# Sheet0-MCU.net
KiCad netlist of a schematic drawn in Altium Designer
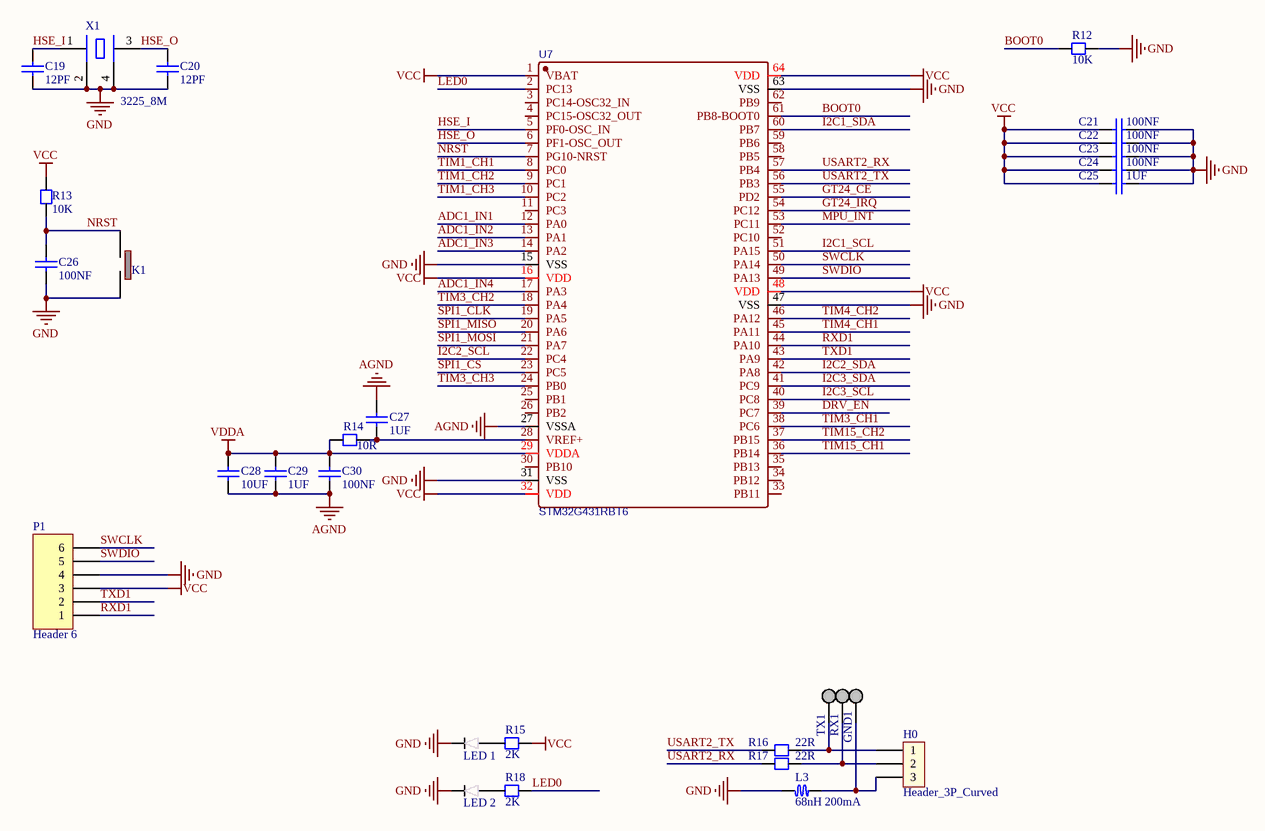
[diagram p0: Sheet0-MCU.SchDoc]

(export (version "E")
  (design (tool "Eeschema 10.0.6"))
  (components
    (comp (ref "C19")
      (value "12PF")
      (footprint "CC1608-0603")
      (description "0603封装的电容")
      (fields (field (name "PUBLISHER") "Altium Limited"))
      (libsource (lib "base") (part "Cap Chip 0603"))
    )
    (comp (ref "C20")
      (value "12PF")
      (footprint "CC1608-0603")
      (description "0603封装的电容")
      (fields (field (name "PUBLISHER") "Altium Limited"))
      (libsource (lib "base") (part "Cap Chip 0603"))
    )
    (comp (ref "C21")
      (value "100NF")
      (footprint "CC1608-0603")
      (description "0603封装的电容")
      (fields (field (name "PUBLISHER") "Altium Limited"))
      (libsource (lib "base") (part "Cap Chip 0603"))
    )
    (comp (ref "C22")
      (value "100NF")
      (footprint "CC1608-0603")
      (description "0603封装的电容")
      (fields (field (name "PUBLISHER") "Altium Limited"))
      (libsource (lib "base") (part "Cap Chip 0603"))
    )
    (comp (ref "C23")
      (value "100NF")
      (footprint "CC1608-0603")
      (description "0603封装的电容")
      (fields (field (name "PUBLISHER") "Altium Limited"))
      (libsource (lib "base") (part "Cap Chip 0603"))
    )
    (comp (ref "C24")
      (value "100NF")
      (footprint "CC1608-0603")
      (description "0603封装的电容")
      (fields (field (name "PUBLISHER") "Altium Limited"))
      (libsource (lib "base") (part "Cap Chip 0603"))
    )
    (comp (ref "C25")
      (value "1UF")
      (footprint "CC1608-0603")
      (description "0603封装的电容")
      (fields (field (name "PUBLISHER") "Altium Limited"))
      (libsource (lib "base") (part "Cap Chip 0603"))
    )
    (comp (ref "C26")
      (value "100NF")
      (footprint "CC1608-0603")
      (description "0603封装的电容")
      (fields (field (name "PUBLISHER") "Altium Limited"))
      (libsource (lib "base") (part "Cap Chip 0603"))
    )
    (comp (ref "C27")
      (value "1UF")
      (footprint "CC1608-0603")
      (description "0603封装的电容")
      (fields (field (name "PUBLISHER") "Altium Limited"))
      (libsource (lib "base") (part "Cap Chip 0603"))
    )
    (comp (ref "C28")
      (value "10UF")
      (footprint "CC1608-0603")
      (description "0603封装的电容")
      (fields (field (name "PUBLISHER") "Altium Limited"))
      (libsource (lib "base") (part "Cap Chip 0603"))
    )
    (comp (ref "C29")
      (value "1UF")
      (footprint "CC1608-0603")
      (description "0603封装的电容")
      (fields (field (name "PUBLISHER") "Altium Limited"))
      (libsource (lib "base") (part "Cap Chip 0603"))
    )
    (comp (ref "C30")
      (value "100NF")
      (footprint "CC1608-0603")
      (description "0603封装的电容")
      (fields (field (name "PUBLISHER") "Altium Limited"))
      (libsource (lib "base") (part "Cap Chip 0603"))
    )
    (comp (ref "GND1")
      (value "test")
      (footprint "test")
      (description "测试点")
      (libsource (lib "base") (part "test"))
    )
    (comp (ref "H0")
      (value "Header_3P_Curved")
      (footprint "Header_2_54_3PW")
      (description "弯的3P排针")
      (libsource (lib "base") (part "Header_3P_Curved"))
    )
    (comp (ref "K1")
      (value "KEY 3*4")
      (footprint "KEY 3*4")
      (description "轻触开关按键")
      (libsource (lib "base") (part "KEY 3*4"))
    )
    (comp (ref "L3")
      (value "68nH 200mA")
      (footprint "Inductor-0603")
      (description "贴片电感 0603封装")
      (libsource (lib "base") (part "Inductor-0603"))
    )
    (comp (ref "LED 1") (value "LED 0603") (footprint "LED 0603") (libsource (lib "base") (part "LED 0603")))
    (comp (ref "LED 2") (value "LED 0603") (footprint "LED 0603") (libsource (lib "base") (part "LED 0603")))
    (comp (ref "P1")
      (value "Header 6")
      (footprint "HDR1X6")
      (description "Header, 6-Pin")
      (fields (field (name "PUBLISHER") "Altium Limited"))
      (libsource (lib "Connectors") (part "Header 6"))
    )
    (comp (ref "R12")
      (value "10K")
      (footprint "CR1608-0603")
      (description "0603封装电阻")
      (fields (field (name "PUBLISHER") "Altium Limited"))
      (libsource (lib "base") (part "Resistor Chip 0603"))
    )
    (comp (ref "R13")
      (value "10K")
      (footprint "CR1608-0603")
      (description "0603封装电阻")
      (fields (field (name "PUBLISHER") "Altium Limited"))
      (libsource (lib "") (part "Resistor Chip 0603_2"))
    )
    (comp (ref "R14")
      (value "10R")
      (footprint "CR1608-0603")
      (description "0603封装电阻")
      (fields (field (name "PUBLISHER") "Altium Limited"))
      (libsource (lib "base") (part "Resistor Chip 0603"))
    )
    (comp (ref "R15")
      (value "2K")
      (footprint "CR1608-0603")
      (description "0603封装电阻")
      (fields (field (name "PUBLISHER") "Altium Limited"))
      (libsource (lib "") (part "Resistor Chip 0603_1"))
    )
    (comp (ref "R16")
      (value "22R")
      (footprint "CR1608-0603")
      (description "0603封装电阻")
      (fields (field (name "PUBLISHER") "Altium Limited"))
      (libsource (lib "") (part "Resistor Chip 0603_1"))
    )
    (comp (ref "R17")
      (value "22R")
      (footprint "CR1608-0603")
      (description "0603封装电阻")
      (fields (field (name "PUBLISHER") "Altium Limited"))
      (libsource (lib "") (part "Resistor Chip 0603_1"))
    )
    (comp (ref "R18")
      (value "2K")
      (footprint "CR1608-0603")
      (description "0603封装电阻")
      (fields (field (name "PUBLISHER") "Altium Limited"))
      (libsource (lib "") (part "Resistor Chip 0603_1"))
    )
    (comp (ref "RX1")
      (value "test")
      (footprint "test")
      (description "测试点")
      (libsource (lib "base") (part "test"))
    )
    (comp (ref "TX1")
      (value "test")
      (footprint "test")
      (description "测试点")
      (libsource (lib "base") (part "test"))
    )
    (comp (ref "U7")
      (value "STM32G431RBT6")
      (footprint "LQFP-64")
      (fields (field (name "MANUFACTURER") "ST(意法半导体)") (field (name "CONTRIBUTOR") "LCSC"))
      (libsource (lib "singlechip") (part "STM32G431RBT6"))
    )
    (comp (ref "X1")
      (value "3225_8M")
      (footprint "XTAL-3225")
      (description "3225封装的晶振")
      (libsource (lib "base") (part "XTAL 3225"))
    )
  )
  (nets
    (net (code "1") (name "/ADC1_IN1") (class "Default")
      (node (ref "U7") (pin "12") (pinfunction "PA0_12") (pintype "passive"))
    )
    (net (code "2") (name "/ADC1_IN2") (class "Default")
      (node (ref "U7") (pin "13") (pinfunction "PA1_13") (pintype "passive"))
    )
    (net (code "3") (name "/ADC1_IN3") (class "Default")
      (node (ref "U7") (pin "14") (pinfunction "PA2_14") (pintype "passive"))
    )
    (net (code "4") (name "/ADC1_IN4") (class "Default")
      (node (ref "U7") (pin "17") (pinfunction "PA3_17") (pintype "passive"))
    )
    (net (code "5") (name "/BOOT0") (class "Default")
      (node (ref "R12") (pin "2") (pinfunction "2_2") (pintype "passive"))
      (node (ref "U7") (pin "61") (pinfunction "PB8-BOOT0_61") (pintype "passive"))
    )
    (net (code "6") (name "/DRV_EN") (class "Default")
      (node (ref "U7") (pin "39") (pinfunction "PC7_39") (pintype "passive"))
    )
    (net (code "7") (name "/GT24_CE") (class "Default")
      (node (ref "U7") (pin "55") (pinfunction "PD2_55") (pintype "passive"))
    )
    (net (code "8") (name "/GT24_IRQ") (class "Default")
      (node (ref "U7") (pin "54") (pinfunction "PC12_54") (pintype "passive"))
    )
    (net (code "9") (name "/HSE_I") (class "Default")
      (node (ref "C19") (pin "2") (pinfunction "2_2") (pintype "passive"))
      (node (ref "U7") (pin "5") (pinfunction "PF0-OSC_IN_5") (pintype "passive"))
      (node (ref "X1") (pin "1") (pinfunction "OSC1_1") (pintype "passive"))
    )
    (net (code "10") (name "/HSE_O") (class "Default")
      (node (ref "C20") (pin "2") (pinfunction "2_2") (pintype "passive"))
      (node (ref "U7") (pin "6") (pinfunction "PF1-OSC_OUT_6") (pintype "passive"))
      (node (ref "X1") (pin "3") (pinfunction "OSC2_3") (pintype "passive"))
    )
    (net (code "11") (name "/I2C1_SCL") (class "Default")
      (node (ref "U7") (pin "51") (pinfunction "PA15_51") (pintype "passive"))
    )
    (net (code "12") (name "/I2C1_SDA") (class "Default")
      (node (ref "U7") (pin "60") (pinfunction "PB7_60") (pintype "passive"))
    )
    (net (code "13") (name "/I2C2_SCL") (class "Default")
      (node (ref "U7") (pin "22") (pinfunction "PC4_22") (pintype "passive"))
    )
    (net (code "14") (name "/I2C2_SDA") (class "Default")
      (node (ref "U7") (pin "42") (pinfunction "PA8_42") (pintype "passive"))
    )
    (net (code "15") (name "/I2C3_SCL") (class "Default")
      (node (ref "U7") (pin "40") (pinfunction "PC8_40") (pintype "passive"))
    )
    (net (code "16") (name "/I2C3_SDA") (class "Default")
      (node (ref "U7") (pin "41") (pinfunction "PC9_41") (pintype "passive"))
    )
    (net (code "17") (name "/LED0") (class "Default")
      (node (ref "R18") (pin "2") (pinfunction "2_2") (pintype "passive"))
      (node (ref "U7") (pin "2") (pinfunction "PC13_2") (pintype "passive"))
    )
    (net (code "18") (name "/MPU_INT") (class "Default")
      (node (ref "U7") (pin "53") (pinfunction "PC11_53") (pintype "passive"))
    )
    (net (code "19") (name "/NRST") (class "Default")
      (node (ref "C26") (pin "2") (pinfunction "2_2") (pintype "passive"))
      (node (ref "K1") (pin "1") (pinfunction "1_1") (pintype "passive"))
      (node (ref "R13") (pin "1") (pinfunction "1_1") (pintype "passive"))
      (node (ref "U7") (pin "7") (pinfunction "PG10-NRST_7") (pintype "passive"))
    )
    (net (code "20") (name "/RXD1") (class "Default")
      (node (ref "P1") (pin "1") (pinfunction "1_1") (pintype "passive"))
      (node (ref "U7") (pin "44") (pinfunction "PA10_44") (pintype "passive"))
    )
    (net (code "21") (name "/SPI1_CLK") (class "Default")
      (node (ref "U7") (pin "19") (pinfunction "PA5_19") (pintype "passive"))
    )
    (net (code "22") (name "/SPI1_CS") (class "Default")
      (node (ref "U7") (pin "23") (pinfunction "PC5_23") (pintype "passive"))
    )
    (net (code "23") (name "/SPI1_MISO") (class "Default")
      (node (ref "U7") (pin "20") (pinfunction "PA6_20") (pintype "passive"))
    )
    (net (code "24") (name "/SPI1_MOSI") (class "Default")
      (node (ref "U7") (pin "21") (pinfunction "PA7_21") (pintype "passive"))
    )
    (net (code "25") (name "/SWCLK") (class "Default")
      (node (ref "P1") (pin "6") (pinfunction "6_6") (pintype "passive"))
      (node (ref "U7") (pin "50") (pinfunction "PA14_50") (pintype "passive"))
    )
    (net (code "26") (name "/SWDIO") (class "Default")
      (node (ref "P1") (pin "5") (pinfunction "5_5") (pintype "passive"))
      (node (ref "U7") (pin "49") (pinfunction "PA13_49") (pintype "passive"))
    )
    (net (code "27") (name "/TIM1_CH1") (class "Default")
      (node (ref "U7") (pin "8") (pinfunction "PC0_8") (pintype "passive"))
    )
    (net (code "28") (name "/TIM1_CH2") (class "Default")
      (node (ref "U7") (pin "9") (pinfunction "PC1_9") (pintype "passive"))
    )
    (net (code "29") (name "/TIM1_CH3") (class "Default")
      (node (ref "U7") (pin "10") (pinfunction "PC2_10") (pintype "passive"))
    )
    (net (code "30") (name "/TIM3_CH1") (class "Default")
      (node (ref "U7") (pin "38") (pinfunction "PC6_38") (pintype "passive"))
    )
    (net (code "31") (name "/TIM3_CH2") (class "Default")
      (node (ref "U7") (pin "18") (pinfunction "PA4_18") (pintype "passive"))
    )
    (net (code "32") (name "/TIM3_CH3") (class "Default")
      (node (ref "U7") (pin "24") (pinfunction "PB0_24") (pintype "passive"))
    )
    (net (code "33") (name "/TIM4_CH1") (class "Default")
      (node (ref "U7") (pin "45") (pinfunction "PA11_45") (pintype "passive"))
    )
    (net (code "34") (name "/TIM4_CH2") (class "Default")
      (node (ref "U7") (pin "46") (pinfunction "PA12_46") (pintype "passive"))
    )
    (net (code "35") (name "/TIM15_CH1") (class "Default")
      (node (ref "U7") (pin "36") (pinfunction "PB14_36") (pintype "passive"))
    )
    (net (code "36") (name "/TIM15_CH2") (class "Default")
      (node (ref "U7") (pin "37") (pinfunction "PB15_37") (pintype "passive"))
    )
    (net (code "37") (name "/TXD1") (class "Default")
      (node (ref "P1") (pin "2") (pinfunction "2_2") (pintype "passive"))
      (node (ref "U7") (pin "43") (pinfunction "PA9_43") (pintype "passive"))
    )
    (net (code "38") (name "/USART2_RX") (class "Default")
      (node (ref "R17") (pin "1") (pinfunction "1_1") (pintype "passive"))
      (node (ref "U7") (pin "57") (pinfunction "PB4_57") (pintype "passive"))
    )
    (net (code "39") (name "/USART2_TX") (class "Default")
      (node (ref "R16") (pin "1") (pinfunction "1_1") (pintype "passive"))
      (node (ref "U7") (pin "56") (pinfunction "PB3_56") (pintype "passive"))
    )
    (net (code "40") (name "AGND") (class "Default")
      (node (ref "C27") (pin "1") (pinfunction "1_1") (pintype "passive"))
      (node (ref "C28") (pin "1") (pinfunction "1_1") (pintype "passive"))
      (node (ref "C29") (pin "1") (pinfunction "1_1") (pintype "passive"))
      (node (ref "C30") (pin "1") (pinfunction "1_1") (pintype "passive"))
      (node (ref "U7") (pin "27") (pinfunction "VSSA_27") (pintype "passive"))
    )
    (net (code "41") (name "GND") (class "Default")
      (node (ref "C19") (pin "1") (pinfunction "1_1") (pintype "passive"))
      (node (ref "C20") (pin "1") (pinfunction "1_1") (pintype "passive"))
      (node (ref "C21") (pin "1") (pinfunction "1_1") (pintype "passive"))
      (node (ref "C22") (pin "1") (pinfunction "1_1") (pintype "passive"))
      (node (ref "C23") (pin "1") (pinfunction "1_1") (pintype "passive"))
      (node (ref "C24") (pin "1") (pinfunction "1_1") (pintype "passive"))
      (node (ref "C25") (pin "1") (pinfunction "1_1") (pintype "passive"))
      (node (ref "C26") (pin "1") (pinfunction "1_1") (pintype "passive"))
      (node (ref "K1") (pin "2") (pinfunction "2_2") (pintype "passive"))
      (node (ref "L3") (pin "2") (pinfunction "2_2") (pintype "passive"))
      (node (ref "LED 1") (pin "2") (pinfunction "2_2") (pintype "passive"))
      (node (ref "LED 2") (pin "2") (pinfunction "2_2") (pintype "passive"))
      (node (ref "P1") (pin "4") (pinfunction "4_4") (pintype "passive"))
      (node (ref "R12") (pin "1") (pinfunction "1_1") (pintype "passive"))
      (node (ref "U7") (pin "15") (pinfunction "VSS_15") (pintype "passive"))
      (node (ref "U7") (pin "31") (pinfunction "VSS_31") (pintype "passive"))
      (node (ref "U7") (pin "47") (pinfunction "VSS_47") (pintype "passive"))
      (node (ref "U7") (pin "63") (pinfunction "VSS_63") (pintype "passive"))
      (node (ref "X1") (pin "2") (pinfunction "GND_2") (pintype "passive"))
      (node (ref "X1") (pin "4") (pinfunction "GND_4") (pintype "passive"))
    )
    (net (code "42") (name "Net-(GND1-Pad0)") (class "Default")
      (node (ref "GND1") (pin "0") (pinfunction "0_0") (pintype "passive"))
      (node (ref "H0") (pin "3") (pinfunction "3_3") (pintype "passive"))
      (node (ref "L3") (pin "1") (pinfunction "1_1") (pintype "passive"))
    )
    (net (code "43") (name "Net-(H0-Pad1)") (class "Default")
      (node (ref "H0") (pin "1") (pinfunction "1_1") (pintype "passive"))
      (node (ref "R16") (pin "2") (pinfunction "2_2") (pintype "passive"))
      (node (ref "TX1") (pin "0") (pinfunction "0_0") (pintype "passive"))
    )
    (net (code "44") (name "Net-(H0-Pad2)") (class "Default")
      (node (ref "H0") (pin "2") (pinfunction "2_2") (pintype "passive"))
      (node (ref "R17") (pin "2") (pinfunction "2_2") (pintype "passive"))
      (node (ref "RX1") (pin "0") (pinfunction "0_0") (pintype "passive"))
    )
    (net (code "45") (name "Net-(LED 1-Pad1)") (class "Default")
      (node (ref "LED 1") (pin "1") (pinfunction "1_1") (pintype "passive"))
      (node (ref "R15") (pin "1") (pinfunction "1_1") (pintype "passive"))
    )
    (net (code "46") (name "Net-(LED 2-Pad1)") (class "Default")
      (node (ref "LED 2") (pin "1") (pinfunction "1_1") (pintype "passive"))
      (node (ref "R18") (pin "1") (pinfunction "1_1") (pintype "passive"))
    )
    (net (code "47") (name "Net-(U7-VREF+)") (class "Default")
      (node (ref "C27") (pin "2") (pinfunction "2_2") (pintype "passive"))
      (node (ref "R14") (pin "1") (pinfunction "1_1") (pintype "passive"))
      (node (ref "U7") (pin "28") (pinfunction "VREF+_28") (pintype "passive"))
    )
    (net (code "48") (name "VCC") (class "Default")
      (node (ref "C21") (pin "2") (pinfunction "2_2") (pintype "passive"))
      (node (ref "C22") (pin "2") (pinfunction "2_2") (pintype "passive"))
      (node (ref "C23") (pin "2") (pinfunction "2_2") (pintype "passive"))
      (node (ref "C24") (pin "2") (pinfunction "2_2") (pintype "passive"))
      (node (ref "C25") (pin "2") (pinfunction "2_2") (pintype "passive"))
      (node (ref "P1") (pin "3") (pinfunction "3_3") (pintype "passive"))
      (node (ref "R13") (pin "2") (pinfunction "2_2") (pintype "passive"))
      (node (ref "R15") (pin "2") (pinfunction "2_2") (pintype "passive"))
      (node (ref "U7") (pin "1") (pinfunction "VBAT_1") (pintype "passive"))
      (node (ref "U7") (pin "16") (pinfunction "VDD_16") (pintype "passive"))
      (node (ref "U7") (pin "32") (pinfunction "VDD_32") (pintype "passive"))
      (node (ref "U7") (pin "48") (pinfunction "VDD_48") (pintype "passive"))
      (node (ref "U7") (pin "64") (pinfunction "VDD_64") (pintype "passive"))
    )
    (net (code "49") (name "VDDA") (class "Default")
      (node (ref "C28") (pin "2") (pinfunction "2_2") (pintype "passive"))
      (node (ref "C29") (pin "2") (pinfunction "2_2") (pintype "passive"))
      (node (ref "C30") (pin "2") (pinfunction "2_2") (pintype "passive"))
      (node (ref "R14") (pin "2") (pinfunction "2_2") (pintype "passive"))
      (node (ref "U7") (pin "29") (pinfunction "VDDA_29") (pintype "passive"))
    )
    (net (code "50") (name "unconnected-(U7-PB1-Pad25)") (class "Default")
      (node (ref "U7") (pin "25") (pinfunction "PB1_25") (pintype "passive"))
    )
    (net (code "51") (name "unconnected-(U7-PB2-Pad26)") (class "Default")
      (node (ref "U7") (pin "26") (pinfunction "PB2_26") (pintype "passive"))
    )
    (net (code "52") (name "unconnected-(U7-PB5-Pad58)") (class "Default")
      (node (ref "U7") (pin "58") (pinfunction "PB5_58") (pintype "passive"))
    )
    (net (code "53") (name "unconnected-(U7-PB6-Pad59)") (class "Default")
      (node (ref "U7") (pin "59") (pinfunction "PB6_59") (pintype "passive"))
    )
    (net (code "54") (name "unconnected-(U7-PB9-Pad62)") (class "Default")
      (node (ref "U7") (pin "62") (pinfunction "PB9_62") (pintype "passive"))
    )
    (net (code "55") (name "unconnected-(U7-PB10-Pad30)") (class "Default")
      (node (ref "U7") (pin "30") (pinfunction "PB10_30") (pintype "passive"))
    )
    (net (code "56") (name "unconnected-(U7-PB11-Pad33)") (class "Default")
      (node (ref "U7") (pin "33") (pinfunction "PB11_33") (pintype "passive"))
    )
    (net (code "57") (name "unconnected-(U7-PB12-Pad34)") (class "Default")
      (node (ref "U7") (pin "34") (pinfunction "PB12_34") (pintype "passive"))
    )
    (net (code "58") (name "unconnected-(U7-PB13-Pad35)") (class "Default")
      (node (ref "U7") (pin "35") (pinfunction "PB13_35") (pintype "passive"))
    )
    (net (code "59") (name "unconnected-(U7-PC3-Pad11)") (class "Default")
      (node (ref "U7") (pin "11") (pinfunction "PC3_11") (pintype "passive"))
    )
    (net (code "60") (name "unconnected-(U7-PC10-Pad52)") (class "Default")
      (node (ref "U7") (pin "52") (pinfunction "PC10_52") (pintype "passive"))
    )
    (net (code "61") (name "unconnected-(U7-PC14-OSC32_IN-Pad3)") (class "Default")
      (node (ref "U7") (pin "3") (pinfunction "PC14-OSC32_IN_3") (pintype "passive"))
    )
    (net (code "62") (name "unconnected-(U7-PC15-OSC32_OUT-Pad4)") (class "Default")
      (node (ref "U7") (pin "4") (pinfunction "PC15-OSC32_OUT_4") (pintype "passive"))
    )
  )
)
